# R409J.net
KiCad netlist of a schematic drawn in EAGLE
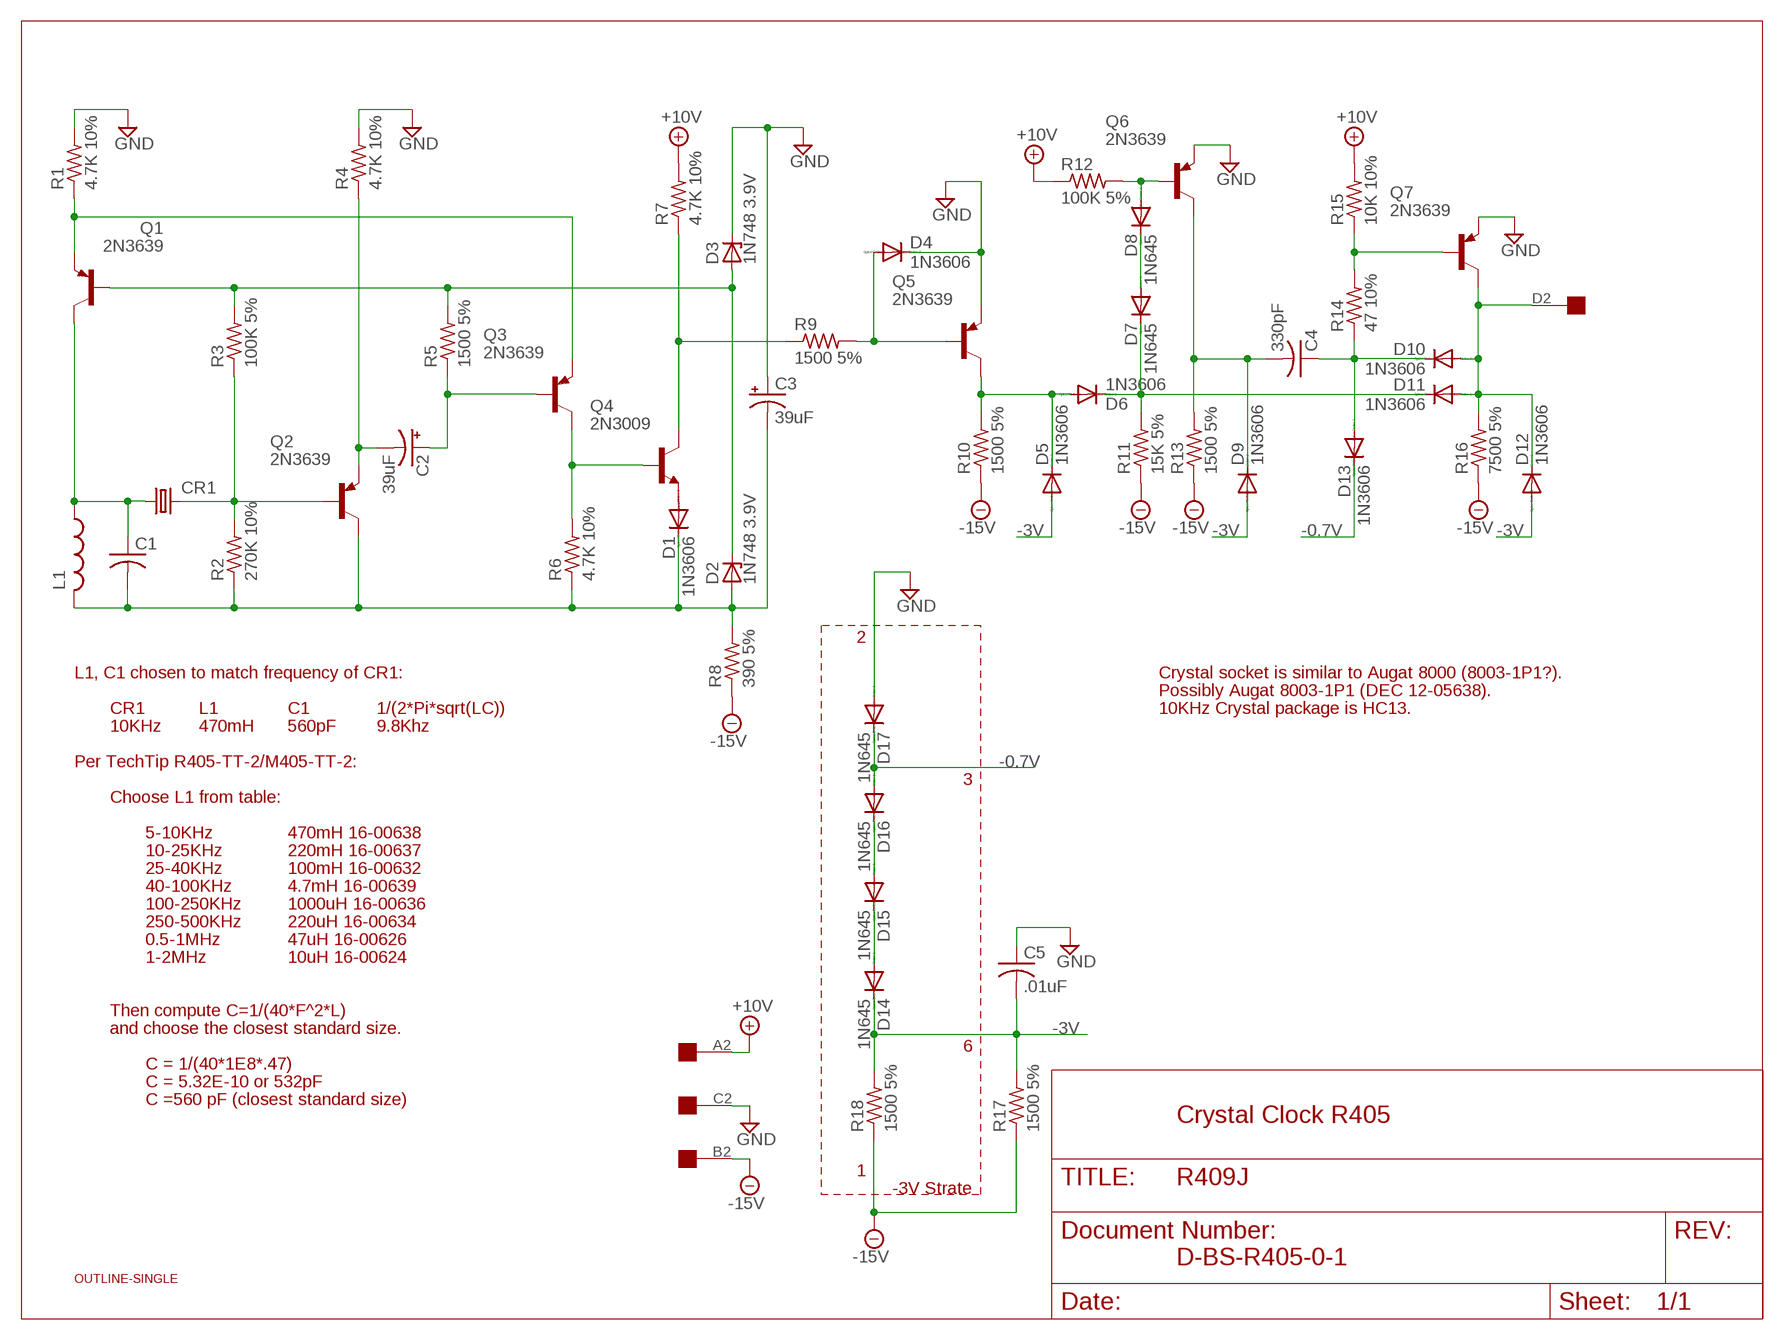
[diagram p0: schematic, sheet 1]

(export (version "E")
  (design (tool "Eeschema 10.0.6"))
  (components
    (comp (ref "C1")
      (value "C-US150-054X183")
      (footprint "eagle-import:C150-054X183")
      (libsource (lib "eagle-import") (part "C-US150-054X183"))
    )
    (comp (ref "C2")
      (value "39uF")
      (footprint "eagle-import:E15-5")
      (libsource (lib "eagle-import") (part "CPOL-USE15-5AXIAL"))
    )
    (comp (ref "C3")
      (value "39uF")
      (footprint "eagle-import:E15-5")
      (libsource (lib "eagle-import") (part "CPOL-USE15-5AXIAL"))
    )
    (comp (ref "C4")
      (value "330pF")
      (footprint "eagle-import:C150-054X183")
      (libsource (lib "eagle-import") (part "C-US150-054X183"))
    )
    (comp (ref "C5")
      (value ".01uF")
      (footprint "eagle-import:C150-054X183")
      (libsource (lib "eagle-import") (part "C-US150-054X183"))
    )
    (comp (ref "CR1")
      (value "CRYSTALHC13U-H")
      (footprint "eagle-import:HC13U-H")
      (libsource (lib "eagle-import") (part "CRYSTALHC13U-H"))
    )
    (comp (ref "D1")
      (value "1N3606")
      (footprint "eagle-import:DO35-10")
      (libsource (lib "eagle-import") (part "1N4148DO35-10"))
    )
    (comp (ref "D2")
      (value "1N748 3.9V")
      (footprint "eagle-import:DO35Z10")
      (libsource (lib "eagle-import") (part "ZENER-DIODEDO35Z10"))
    )
    (comp (ref "D3")
      (value "1N748 3.9V")
      (footprint "eagle-import:DO35Z10")
      (libsource (lib "eagle-import") (part "ZENER-DIODEDO35Z10"))
    )
    (comp (ref "D4")
      (value "1N3606")
      (footprint "eagle-import:DO35-10")
      (libsource (lib "eagle-import") (part "1N4148DO35-10"))
    )
    (comp (ref "D5")
      (value "1N3606")
      (footprint "eagle-import:DO35-10")
      (libsource (lib "eagle-import") (part "1N4148DO35-10"))
    )
    (comp (ref "D6")
      (value "1N3606")
      (footprint "eagle-import:DO35-10")
      (libsource (lib "eagle-import") (part "1N4148DO35-10"))
    )
    (comp (ref "D7")
      (value "1N645")
      (footprint "eagle-import:DO35-10")
      (libsource (lib "eagle-import") (part "1N4148DO35-10"))
    )
    (comp (ref "D8")
      (value "1N645")
      (footprint "eagle-import:DO35-10")
      (libsource (lib "eagle-import") (part "1N4148DO35-10"))
    )
    (comp (ref "D9")
      (value "1N3606")
      (footprint "eagle-import:DO35-10")
      (libsource (lib "eagle-import") (part "1N4148DO35-10"))
    )
    (comp (ref "D10")
      (value "1N3606")
      (footprint "eagle-import:DO35-10")
      (libsource (lib "eagle-import") (part "1N4148DO35-10"))
    )
    (comp (ref "D11")
      (value "1N3606")
      (footprint "eagle-import:DO35-10")
      (libsource (lib "eagle-import") (part "1N4148DO35-10"))
    )
    (comp (ref "D12")
      (value "1N3606")
      (footprint "eagle-import:DO35-10")
      (libsource (lib "eagle-import") (part "1N4148DO35-10"))
    )
    (comp (ref "D13")
      (value "1N3606")
      (footprint "eagle-import:DO35-10")
      (libsource (lib "eagle-import") (part "1N4148DO35-10"))
    )
    (comp (ref "D14")
      (value "1N645")
      (footprint "eagle-import:DO35-10")
      (libsource (lib "eagle-import") (part "1N4148DO35-10"))
    )
    (comp (ref "D15")
      (value "1N645")
      (footprint "eagle-import:DO35-10")
      (libsource (lib "eagle-import") (part "1N4148DO35-10"))
    )
    (comp (ref "D16")
      (value "1N645")
      (footprint "eagle-import:DO35-10")
      (libsource (lib "eagle-import") (part "1N4148DO35-10"))
    )
    (comp (ref "D17")
      (value "1N645")
      (footprint "eagle-import:DO35-10")
      (libsource (lib "eagle-import") (part "1N4148DO35-10"))
    )
    (comp (ref "L1")
      (value "L-US0207/7")
      (footprint "eagle-import:0207_7")
      (libsource (lib "eagle-import") (part "L-US0207/7"))
    )
    (comp (ref "Q1")
      (value "2N3639")
      (footprint "eagle-import:TO39")
      (libsource (lib "eagle-import") (part "2N2904"))
    )
    (comp (ref "Q2")
      (value "2N3639")
      (footprint "eagle-import:TO39")
      (libsource (lib "eagle-import") (part "2N2904"))
    )
    (comp (ref "Q3")
      (value "2N3639")
      (footprint "eagle-import:TO39")
      (libsource (lib "eagle-import") (part "2N2904"))
    )
    (comp (ref "Q4")
      (value "2N3009")
      (footprint "eagle-import:TO5")
      (libsource (lib "eagle-import") (part "2N2102"))
    )
    (comp (ref "Q5")
      (value "2N3639")
      (footprint "eagle-import:TO39")
      (libsource (lib "eagle-import") (part "2N2904"))
    )
    (comp (ref "Q6")
      (value "2N3639")
      (footprint "eagle-import:TO39")
      (libsource (lib "eagle-import") (part "2N2904"))
    )
    (comp (ref "Q7")
      (value "2N3639")
      (footprint "eagle-import:TO39")
      (libsource (lib "eagle-import") (part "2N2904"))
    )
    (comp (ref "R1")
      (value "4.7K 10%")
      (footprint "eagle-import:0207_10")
      (libsource (lib "eagle-import") (part "R-US_0207/10"))
    )
    (comp (ref "R2")
      (value "270K 10%")
      (footprint "eagle-import:0207_10")
      (libsource (lib "eagle-import") (part "R-US_0207/10"))
    )
    (comp (ref "R3")
      (value "100K 5%")
      (footprint "eagle-import:0207_10")
      (libsource (lib "eagle-import") (part "R-US_0207/10"))
    )
    (comp (ref "R4")
      (value "4.7K 10%")
      (footprint "eagle-import:0207_10")
      (libsource (lib "eagle-import") (part "R-US_0207/10"))
    )
    (comp (ref "R5")
      (value "1500 5%")
      (footprint "eagle-import:0207_10")
      (libsource (lib "eagle-import") (part "R-US_0207/10"))
    )
    (comp (ref "R6")
      (value "4.7K 10%")
      (footprint "eagle-import:0207_10")
      (libsource (lib "eagle-import") (part "R-US_0207/10"))
    )
    (comp (ref "R7")
      (value "4.7K 10%")
      (footprint "eagle-import:0207_10")
      (libsource (lib "eagle-import") (part "R-US_0207/10"))
    )
    (comp (ref "R8")
      (value "390 5%")
      (footprint "eagle-import:0207_10")
      (libsource (lib "eagle-import") (part "R-US_0207/10"))
    )
    (comp (ref "R9")
      (value "1500 5%")
      (footprint "eagle-import:0207_10")
      (libsource (lib "eagle-import") (part "R-US_0207/10"))
    )
    (comp (ref "R10")
      (value "1500 5%")
      (footprint "eagle-import:0207_10")
      (libsource (lib "eagle-import") (part "R-US_0207/10"))
    )
    (comp (ref "R11")
      (value "15K 5%")
      (footprint "eagle-import:0207_10")
      (libsource (lib "eagle-import") (part "R-US_0207/10"))
    )
    (comp (ref "R12")
      (value "100K 5%")
      (footprint "eagle-import:0207_10")
      (libsource (lib "eagle-import") (part "R-US_0207/10"))
    )
    (comp (ref "R13")
      (value "1500 5%")
      (footprint "eagle-import:0207_10")
      (libsource (lib "eagle-import") (part "R-US_0207/10"))
    )
    (comp (ref "R14")
      (value "47 10%")
      (footprint "eagle-import:0207_10")
      (libsource (lib "eagle-import") (part "R-US_0207/10"))
    )
    (comp (ref "R15")
      (value "10K 10%")
      (footprint "eagle-import:0207_10")
      (libsource (lib "eagle-import") (part "R-US_0207/10"))
    )
    (comp (ref "R16")
      (value "7500 5%")
      (footprint "eagle-import:0207_10")
      (libsource (lib "eagle-import") (part "R-US_0207/10"))
    )
    (comp (ref "R17")
      (value "1500 5%")
      (footprint "eagle-import:0207_10")
      (libsource (lib "eagle-import") (part "R-US_0207/10"))
    )
    (comp (ref "R18")
      (value "1500 5%")
      (footprint "eagle-import:0207_10")
      (libsource (lib "eagle-import") (part "R-US_0207/10"))
    )
    (comp (ref "U$1")
      (value "OUTLINE-SINGLE")
      (footprint "eagle-import:SINGLE")
      (libsource (lib "eagle-import") (part "OUTLINE-SINGLE"))
    )
    (comp (ref "U$2")
      (value "EDGE-1")
      (footprint "eagle-import:EDGE-CON1")
      (libsource (lib "eagle-import") (part "EDGE-1"))
    )
  )
  (nets
    (net (code "1") (name "+10V") (class "Default")
      (node (ref "R12") (pin "1") (pinfunction "1_1") (pintype "passive"))
      (node (ref "R15") (pin "2") (pinfunction "2_2") (pintype "passive"))
      (node (ref "R7") (pin "2") (pinfunction "2_2") (pintype "passive"))
      (node (ref "U$2") (pin "A2") (pinfunction "1_A2") (pintype "bidirectional"))
    )
    (net (code "2") (name "-15V") (class "Default")
      (node (ref "R10") (pin "1") (pinfunction "1_1") (pintype "passive"))
      (node (ref "R11") (pin "1") (pinfunction "1_1") (pintype "passive"))
      (node (ref "R13") (pin "1") (pinfunction "1_1") (pintype "passive"))
      (node (ref "R16") (pin "1") (pinfunction "1_1") (pintype "passive"))
      (node (ref "R17") (pin "1") (pinfunction "1_1") (pintype "passive"))
      (node (ref "R18") (pin "1") (pinfunction "1_1") (pintype "passive"))
      (node (ref "R8") (pin "1") (pinfunction "1_1") (pintype "passive"))
      (node (ref "U$2") (pin "B2") (pinfunction "1_B2") (pintype "bidirectional"))
    )
    (net (code "3") (name "/-0.7V") (class "Default")
      (node (ref "D13") (pin "C") (pinfunction "C_C") (pintype "passive"))
      (node (ref "D16") (pin "A") (pinfunction "A_A") (pintype "passive"))
      (node (ref "D17") (pin "C") (pinfunction "C_C") (pintype "passive"))
    )
    (net (code "4") (name "/-3V") (class "Default")
      (node (ref "C5") (pin "2") (pinfunction "2_2") (pintype "passive"))
      (node (ref "D12") (pin "A") (pinfunction "A_A") (pintype "passive"))
      (node (ref "D14") (pin "C") (pinfunction "C_C") (pintype "passive"))
      (node (ref "D5") (pin "A") (pinfunction "A_A") (pintype "passive"))
      (node (ref "D9") (pin "A") (pinfunction "A_A") (pintype "passive"))
      (node (ref "R17") (pin "2") (pinfunction "2_2") (pintype "passive"))
      (node (ref "R18") (pin "2") (pinfunction "2_2") (pintype "passive"))
    )
    (net (code "5") (name "GND") (class "Default")
      (node (ref "C3") (pin "+") (pinfunction "+_+") (pintype "passive"))
      (node (ref "C5") (pin "1") (pinfunction "1_1") (pintype "passive"))
      (node (ref "D17") (pin "A") (pinfunction "A_A") (pintype "passive"))
      (node (ref "D3") (pin "C") (pinfunction "C_C") (pintype "passive"))
      (node (ref "D4") (pin "C") (pinfunction "C_C") (pintype "passive"))
      (node (ref "Q5") (pin "1") (pinfunction "E_1") (pintype "passive"))
      (node (ref "Q6") (pin "1") (pinfunction "E_1") (pintype "passive"))
      (node (ref "Q7") (pin "1") (pinfunction "E_1") (pintype "passive"))
      (node (ref "R1") (pin "2") (pinfunction "2_2") (pintype "passive"))
      (node (ref "R4") (pin "2") (pinfunction "2_2") (pintype "passive"))
      (node (ref "U$2") (pin "C2") (pinfunction "1_C2") (pintype "bidirectional"))
    )
    (net (code "6") (name "Net-(C4-Pad1)") (class "Default")
      (node (ref "C4") (pin "1") (pinfunction "1_1") (pintype "passive"))
      (node (ref "D10") (pin "C") (pinfunction "C_C") (pintype "passive"))
      (node (ref "D13") (pin "A") (pinfunction "A_A") (pintype "passive"))
      (node (ref "R14") (pin "1") (pinfunction "1_1") (pintype "passive"))
    )
    (net (code "7") (name "Net-(D7-PadA)") (class "Default")
      (node (ref "D7") (pin "A") (pinfunction "A_A") (pintype "passive"))
      (node (ref "D8") (pin "C") (pinfunction "C_C") (pintype "passive"))
    )
    (net (code "8") (name "Net-(D11-PadC)") (class "Default")
      (node (ref "D11") (pin "C") (pinfunction "C_C") (pintype "passive"))
      (node (ref "D6") (pin "C") (pinfunction "C_C") (pintype "passive"))
      (node (ref "D7") (pin "C") (pinfunction "C_C") (pintype "passive"))
      (node (ref "R11") (pin "2") (pinfunction "2_2") (pintype "passive"))
    )
    (net (code "9") (name "Net-(D14-PadA)") (class "Default")
      (node (ref "D14") (pin "A") (pinfunction "A_A") (pintype "passive"))
      (node (ref "D15") (pin "C") (pinfunction "C_C") (pintype "passive"))
    )
    (net (code "10") (name "Net-(D15-PadA)") (class "Default")
      (node (ref "D15") (pin "A") (pinfunction "A_A") (pintype "passive"))
      (node (ref "D16") (pin "C") (pinfunction "C_C") (pintype "passive"))
    )
    (net (code "11") (name "Net-(Q1-B)") (class "Default")
      (node (ref "D2") (pin "C") (pinfunction "C_C") (pintype "passive"))
      (node (ref "D3") (pin "A") (pinfunction "A_A") (pintype "passive"))
      (node (ref "Q1") (pin "2") (pinfunction "B_2") (pintype "passive"))
      (node (ref "R3") (pin "2") (pinfunction "2_2") (pintype "passive"))
      (node (ref "R5") (pin "2") (pinfunction "2_2") (pintype "passive"))
    )
    (net (code "12") (name "Net-(Q1-C)") (class "Default")
      (node (ref "C1") (pin "1") (pinfunction "1_1") (pintype "passive"))
      (node (ref "CR1") (pin "1") (pinfunction "1_1") (pintype "passive"))
      (node (ref "L1") (pin "1") (pinfunction "1_1") (pintype "passive"))
      (node (ref "Q1") (pin "3") (pinfunction "C_3") (pintype "passive"))
    )
    (net (code "13") (name "Net-(Q1-E)") (class "Default")
      (node (ref "Q1") (pin "1") (pinfunction "E_1") (pintype "passive"))
      (node (ref "Q3") (pin "1") (pinfunction "E_1") (pintype "passive"))
      (node (ref "R1") (pin "1") (pinfunction "1_1") (pintype "passive"))
    )
    (net (code "14") (name "Net-(Q2-B)") (class "Default")
      (node (ref "CR1") (pin "2") (pinfunction "2_2") (pintype "passive"))
      (node (ref "Q2") (pin "2") (pinfunction "B_2") (pintype "passive"))
      (node (ref "R2") (pin "2") (pinfunction "2_2") (pintype "passive"))
      (node (ref "R3") (pin "1") (pinfunction "1_1") (pintype "passive"))
    )
    (net (code "15") (name "Net-(Q2-C)") (class "Default")
      (node (ref "C1") (pin "2") (pinfunction "2_2") (pintype "passive"))
      (node (ref "C3") (pin "-") (pinfunction "-_-") (pintype "passive"))
      (node (ref "D1") (pin "C") (pinfunction "C_C") (pintype "passive"))
      (node (ref "D2") (pin "A") (pinfunction "A_A") (pintype "passive"))
      (node (ref "L1") (pin "2") (pinfunction "2_2") (pintype "passive"))
      (node (ref "Q2") (pin "3") (pinfunction "C_3") (pintype "passive"))
      (node (ref "R2") (pin "1") (pinfunction "1_1") (pintype "passive"))
      (node (ref "R6") (pin "1") (pinfunction "1_1") (pintype "passive"))
      (node (ref "R8") (pin "2") (pinfunction "2_2") (pintype "passive"))
    )
    (net (code "16") (name "Net-(Q2-E)") (class "Default")
      (node (ref "C2") (pin "-") (pinfunction "-_-") (pintype "passive"))
      (node (ref "Q2") (pin "1") (pinfunction "E_1") (pintype "passive"))
      (node (ref "R4") (pin "1") (pinfunction "1_1") (pintype "passive"))
    )
    (net (code "17") (name "Net-(Q3-B)") (class "Default")
      (node (ref "C2") (pin "+") (pinfunction "+_+") (pintype "passive"))
      (node (ref "Q3") (pin "2") (pinfunction "B_2") (pintype "passive"))
      (node (ref "R5") (pin "1") (pinfunction "1_1") (pintype "passive"))
    )
    (net (code "18") (name "Net-(Q3-C)") (class "Default")
      (node (ref "Q3") (pin "3") (pinfunction "C_3") (pintype "passive"))
      (node (ref "Q4") (pin "2") (pinfunction "B_2") (pintype "passive"))
      (node (ref "R6") (pin "2") (pinfunction "2_2") (pintype "passive"))
    )
    (net (code "19") (name "Net-(Q4-C)") (class "Default")
      (node (ref "Q4") (pin "3") (pinfunction "C_3") (pintype "passive"))
      (node (ref "R7") (pin "1") (pinfunction "1_1") (pintype "passive"))
      (node (ref "R9") (pin "1") (pinfunction "1_1") (pintype "passive"))
    )
    (net (code "20") (name "Net-(Q4-E)") (class "Default")
      (node (ref "D1") (pin "A") (pinfunction "A_A") (pintype "passive"))
      (node (ref "Q4") (pin "1") (pinfunction "E_1") (pintype "passive"))
    )
    (net (code "21") (name "Net-(Q5-B)") (class "Default")
      (node (ref "D4") (pin "A") (pinfunction "A_A") (pintype "passive"))
      (node (ref "Q5") (pin "2") (pinfunction "B_2") (pintype "passive"))
      (node (ref "R9") (pin "2") (pinfunction "2_2") (pintype "passive"))
    )
    (net (code "22") (name "Net-(Q5-C)") (class "Default")
      (node (ref "D5") (pin "C") (pinfunction "C_C") (pintype "passive"))
      (node (ref "D6") (pin "A") (pinfunction "A_A") (pintype "passive"))
      (node (ref "Q5") (pin "3") (pinfunction "C_3") (pintype "passive"))
      (node (ref "R10") (pin "2") (pinfunction "2_2") (pintype "passive"))
    )
    (net (code "23") (name "Net-(Q6-B)") (class "Default")
      (node (ref "D8") (pin "A") (pinfunction "A_A") (pintype "passive"))
      (node (ref "Q6") (pin "2") (pinfunction "B_2") (pintype "passive"))
      (node (ref "R12") (pin "2") (pinfunction "2_2") (pintype "passive"))
    )
    (net (code "24") (name "Net-(Q6-C)") (class "Default")
      (node (ref "C4") (pin "2") (pinfunction "2_2") (pintype "passive"))
      (node (ref "D9") (pin "C") (pinfunction "C_C") (pintype "passive"))
      (node (ref "Q6") (pin "3") (pinfunction "C_3") (pintype "passive"))
      (node (ref "R13") (pin "2") (pinfunction "2_2") (pintype "passive"))
    )
    (net (code "25") (name "Net-(Q7-B)") (class "Default")
      (node (ref "Q7") (pin "2") (pinfunction "B_2") (pintype "passive"))
      (node (ref "R14") (pin "2") (pinfunction "2_2") (pintype "passive"))
      (node (ref "R15") (pin "1") (pinfunction "1_1") (pintype "passive"))
    )
    (net (code "26") (name "Net-(Q7-C)") (class "Default")
      (node (ref "D10") (pin "A") (pinfunction "A_A") (pintype "passive"))
      (node (ref "D11") (pin "A") (pinfunction "A_A") (pintype "passive"))
      (node (ref "D12") (pin "C") (pinfunction "C_C") (pintype "passive"))
      (node (ref "Q7") (pin "3") (pinfunction "C_3") (pintype "passive"))
      (node (ref "R16") (pin "2") (pinfunction "2_2") (pintype "passive"))
      (node (ref "U$2") (pin "D2") (pinfunction "1_D2") (pintype "bidirectional"))
    )
  )
)
